# LED24_26.net
KiCad netlist of a schematic drawn in Altium Designer
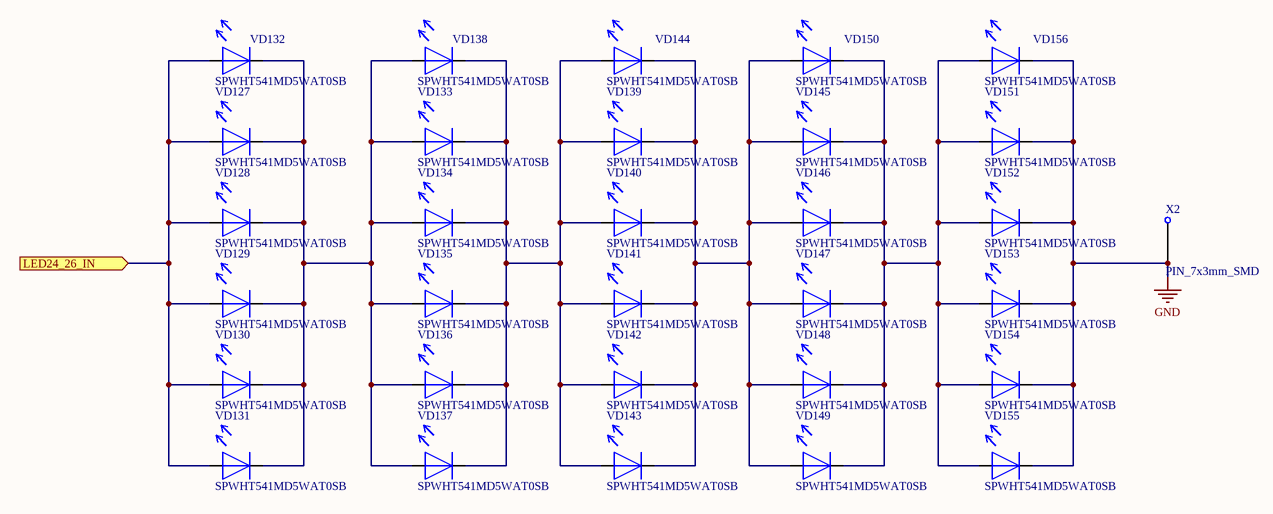
[diagram p0: LED24_26.SchDoc]

(export (version "E")
  (design (tool "Eeschema 10.0.6"))
  (components
    (comp (ref "VD127")
      (value "SPWHT541MD5WAT0SB")
      (footprint "LED_SAMSUNG")
      (libsource (lib "gprs_modem") (part "LED SPWHT541MD5WAT0SB"))
    )
    (comp (ref "VD128")
      (value "SPWHT541MD5WAT0SB")
      (footprint "LED_SAMSUNG")
      (libsource (lib "gprs_modem") (part "LED SPWHT541MD5WAT0SB"))
    )
    (comp (ref "VD129")
      (value "SPWHT541MD5WAT0SB")
      (footprint "LED_SAMSUNG")
      (libsource (lib "gprs_modem") (part "LED SPWHT541MD5WAT0SB"))
    )
    (comp (ref "VD130")
      (value "SPWHT541MD5WAT0SB")
      (footprint "LED_SAMSUNG")
      (libsource (lib "gprs_modem") (part "LED SPWHT541MD5WAT0SB"))
    )
    (comp (ref "VD131")
      (value "SPWHT541MD5WAT0SB")
      (footprint "LED_SAMSUNG")
      (libsource (lib "gprs_modem") (part "LED SPWHT541MD5WAT0SB"))
    )
    (comp (ref "VD132")
      (value "SPWHT541MD5WAT0SB")
      (footprint "LED_SAMSUNG")
      (libsource (lib "gprs_modem") (part "LED SPWHT541MD5WAT0SB"))
    )
    (comp (ref "VD133")
      (value "SPWHT541MD5WAT0SB")
      (footprint "LED_SAMSUNG")
      (libsource (lib "gprs_modem") (part "LED SPWHT541MD5WAT0SB"))
    )
    (comp (ref "VD134")
      (value "SPWHT541MD5WAT0SB")
      (footprint "LED_SAMSUNG")
      (libsource (lib "gprs_modem") (part "LED SPWHT541MD5WAT0SB"))
    )
    (comp (ref "VD135")
      (value "SPWHT541MD5WAT0SB")
      (footprint "LED_SAMSUNG")
      (libsource (lib "gprs_modem") (part "LED SPWHT541MD5WAT0SB"))
    )
    (comp (ref "VD136")
      (value "SPWHT541MD5WAT0SB")
      (footprint "LED_SAMSUNG")
      (libsource (lib "gprs_modem") (part "LED SPWHT541MD5WAT0SB"))
    )
    (comp (ref "VD137")
      (value "SPWHT541MD5WAT0SB")
      (footprint "LED_SAMSUNG")
      (libsource (lib "gprs_modem") (part "LED SPWHT541MD5WAT0SB"))
    )
    (comp (ref "VD138")
      (value "SPWHT541MD5WAT0SB")
      (footprint "LED_SAMSUNG")
      (libsource (lib "gprs_modem") (part "LED SPWHT541MD5WAT0SB"))
    )
    (comp (ref "VD139")
      (value "SPWHT541MD5WAT0SB")
      (footprint "LED_SAMSUNG")
      (libsource (lib "gprs_modem") (part "LED SPWHT541MD5WAT0SB"))
    )
    (comp (ref "VD140")
      (value "SPWHT541MD5WAT0SB")
      (footprint "LED_SAMSUNG")
      (libsource (lib "gprs_modem") (part "LED SPWHT541MD5WAT0SB"))
    )
    (comp (ref "VD141")
      (value "SPWHT541MD5WAT0SB")
      (footprint "LED_SAMSUNG")
      (libsource (lib "gprs_modem") (part "LED SPWHT541MD5WAT0SB"))
    )
    (comp (ref "VD142")
      (value "SPWHT541MD5WAT0SB")
      (footprint "LED_SAMSUNG")
      (libsource (lib "gprs_modem") (part "LED SPWHT541MD5WAT0SB"))
    )
    (comp (ref "VD143")
      (value "SPWHT541MD5WAT0SB")
      (footprint "LED_SAMSUNG")
      (libsource (lib "gprs_modem") (part "LED SPWHT541MD5WAT0SB"))
    )
    (comp (ref "VD144")
      (value "SPWHT541MD5WAT0SB")
      (footprint "LED_SAMSUNG")
      (libsource (lib "gprs_modem") (part "LED SPWHT541MD5WAT0SB"))
    )
    (comp (ref "VD145")
      (value "SPWHT541MD5WAT0SB")
      (footprint "LED_SAMSUNG")
      (libsource (lib "gprs_modem") (part "LED SPWHT541MD5WAT0SB"))
    )
    (comp (ref "VD146")
      (value "SPWHT541MD5WAT0SB")
      (footprint "LED_SAMSUNG")
      (libsource (lib "gprs_modem") (part "LED SPWHT541MD5WAT0SB"))
    )
    (comp (ref "VD147")
      (value "SPWHT541MD5WAT0SB")
      (footprint "LED_SAMSUNG")
      (libsource (lib "gprs_modem") (part "LED SPWHT541MD5WAT0SB"))
    )
    (comp (ref "VD148")
      (value "SPWHT541MD5WAT0SB")
      (footprint "LED_SAMSUNG")
      (libsource (lib "gprs_modem") (part "LED SPWHT541MD5WAT0SB"))
    )
    (comp (ref "VD149")
      (value "SPWHT541MD5WAT0SB")
      (footprint "LED_SAMSUNG")
      (libsource (lib "gprs_modem") (part "LED SPWHT541MD5WAT0SB"))
    )
    (comp (ref "VD150")
      (value "SPWHT541MD5WAT0SB")
      (footprint "LED_SAMSUNG")
      (libsource (lib "gprs_modem") (part "LED SPWHT541MD5WAT0SB"))
    )
    (comp (ref "VD151")
      (value "SPWHT541MD5WAT0SB")
      (footprint "LED_SAMSUNG")
      (libsource (lib "gprs_modem") (part "LED SPWHT541MD5WAT0SB"))
    )
    (comp (ref "VD152")
      (value "SPWHT541MD5WAT0SB")
      (footprint "LED_SAMSUNG")
      (libsource (lib "gprs_modem") (part "LED SPWHT541MD5WAT0SB"))
    )
    (comp (ref "VD153")
      (value "SPWHT541MD5WAT0SB")
      (footprint "LED_SAMSUNG")
      (libsource (lib "gprs_modem") (part "LED SPWHT541MD5WAT0SB"))
    )
    (comp (ref "VD154")
      (value "SPWHT541MD5WAT0SB")
      (footprint "LED_SAMSUNG")
      (libsource (lib "gprs_modem") (part "LED SPWHT541MD5WAT0SB"))
    )
    (comp (ref "VD155")
      (value "SPWHT541MD5WAT0SB")
      (footprint "LED_SAMSUNG")
      (libsource (lib "gprs_modem") (part "LED SPWHT541MD5WAT0SB"))
    )
    (comp (ref "VD156")
      (value "SPWHT541MD5WAT0SB")
      (footprint "LED_SAMSUNG")
      (libsource (lib "gprs_modem") (part "LED SPWHT541MD5WAT0SB"))
    )
    (comp (ref "X2")
      (value "PIN_7x3mm_SMD")
      (footprint "PIN_7x3mm_SMD")
      (libsource (lib "gprs_modem") (part "PIN_7x3mm_SMD"))
    )
  )
  (nets
    (net (code "1") (name "/LED24_26_IN") (class "Default")
      (node (ref "VD127") (pin "1") (pintype "passive"))
      (node (ref "VD128") (pin "1") (pintype "passive"))
      (node (ref "VD129") (pin "1") (pintype "passive"))
      (node (ref "VD130") (pin "1") (pintype "passive"))
      (node (ref "VD131") (pin "1") (pintype "passive"))
      (node (ref "VD132") (pin "1") (pintype "passive"))
    )
    (net (code "2") (name "GND") (class "Default")
      (node (ref "VD151") (pin "2") (pintype "passive"))
      (node (ref "VD152") (pin "2") (pintype "passive"))
      (node (ref "VD153") (pin "2") (pintype "passive"))
      (node (ref "VD154") (pin "2") (pintype "passive"))
      (node (ref "VD155") (pin "2") (pintype "passive"))
      (node (ref "VD156") (pin "2") (pintype "passive"))
      (node (ref "X2") (pin "1") (pinfunction "1_1") (pintype "passive"))
    )
    (net (code "3") (name "Net-(VD127-Pad2)") (class "Default")
      (node (ref "VD127") (pin "2") (pintype "passive"))
      (node (ref "VD128") (pin "2") (pintype "passive"))
      (node (ref "VD129") (pin "2") (pintype "passive"))
      (node (ref "VD130") (pin "2") (pintype "passive"))
      (node (ref "VD131") (pin "2") (pintype "passive"))
      (node (ref "VD132") (pin "2") (pintype "passive"))
      (node (ref "VD133") (pin "1") (pintype "passive"))
      (node (ref "VD134") (pin "1") (pintype "passive"))
      (node (ref "VD135") (pin "1") (pintype "passive"))
      (node (ref "VD136") (pin "1") (pintype "passive"))
      (node (ref "VD137") (pin "1") (pintype "passive"))
      (node (ref "VD138") (pin "1") (pintype "passive"))
    )
    (net (code "4") (name "Net-(VD133-Pad2)") (class "Default")
      (node (ref "VD133") (pin "2") (pintype "passive"))
      (node (ref "VD134") (pin "2") (pintype "passive"))
      (node (ref "VD135") (pin "2") (pintype "passive"))
      (node (ref "VD136") (pin "2") (pintype "passive"))
      (node (ref "VD137") (pin "2") (pintype "passive"))
      (node (ref "VD138") (pin "2") (pintype "passive"))
      (node (ref "VD139") (pin "1") (pintype "passive"))
      (node (ref "VD140") (pin "1") (pintype "passive"))
      (node (ref "VD141") (pin "1") (pintype "passive"))
      (node (ref "VD142") (pin "1") (pintype "passive"))
      (node (ref "VD143") (pin "1") (pintype "passive"))
      (node (ref "VD144") (pin "1") (pintype "passive"))
    )
    (net (code "5") (name "Net-(VD139-Pad2)") (class "Default")
      (node (ref "VD139") (pin "2") (pintype "passive"))
      (node (ref "VD140") (pin "2") (pintype "passive"))
      (node (ref "VD141") (pin "2") (pintype "passive"))
      (node (ref "VD142") (pin "2") (pintype "passive"))
      (node (ref "VD143") (pin "2") (pintype "passive"))
      (node (ref "VD144") (pin "2") (pintype "passive"))
      (node (ref "VD145") (pin "1") (pintype "passive"))
      (node (ref "VD146") (pin "1") (pintype "passive"))
      (node (ref "VD147") (pin "1") (pintype "passive"))
      (node (ref "VD148") (pin "1") (pintype "passive"))
      (node (ref "VD149") (pin "1") (pintype "passive"))
      (node (ref "VD150") (pin "1") (pintype "passive"))
    )
    (net (code "6") (name "Net-(VD145-Pad2)") (class "Default")
      (node (ref "VD145") (pin "2") (pintype "passive"))
      (node (ref "VD146") (pin "2") (pintype "passive"))
      (node (ref "VD147") (pin "2") (pintype "passive"))
      (node (ref "VD148") (pin "2") (pintype "passive"))
      (node (ref "VD149") (pin "2") (pintype "passive"))
      (node (ref "VD150") (pin "2") (pintype "passive"))
      (node (ref "VD151") (pin "1") (pintype "passive"))
      (node (ref "VD152") (pin "1") (pintype "passive"))
      (node (ref "VD153") (pin "1") (pintype "passive"))
      (node (ref "VD154") (pin "1") (pintype "passive"))
      (node (ref "VD155") (pin "1") (pintype "passive"))
      (node (ref "VD156") (pin "1") (pintype "passive"))
    )
  )
)
